# design.net
KiCad netlist of a schematic drawn in Altium Designer
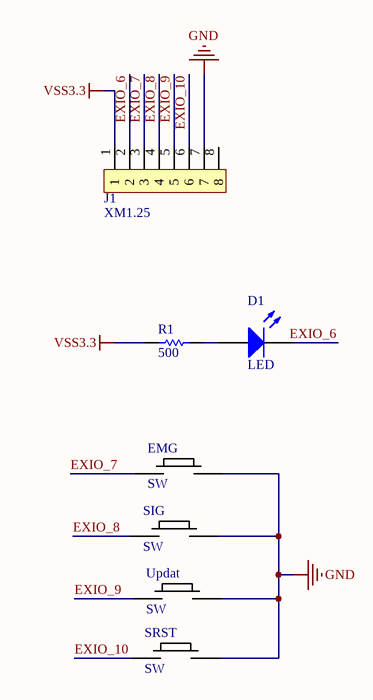
[diagram p0: 遥控器拓展板.SchDoc]

(export (version "E")
  (design (tool "Eeschema 10.0.6"))
  (components
    (comp (ref "D1")
      (value "LED")
      (footprint "LED 0603")
      (description "Typical INFRARED GaAs LED")
      (fields (field (name "PUBLISHER") "Altium Limited"))
      (libsource (lib "Remote") (part "LED"))
    )
    (comp (ref "EMG") (value "SW") (footprint "SW SMD 3x6x2.5") (libsource (lib "船核心板") (part "弹簧开关")))
    (comp (ref "J1")
      (value "XM1.25")
      (footprint "MX1.25 8P")
      (libsource (lib "altium-import") (part "root_0_1X8排针_"))
    )
    (comp (ref "R1")
      (value "500")
      (footprint "R 0603")
      (description "Resistor")
      (fields (field (name "PUBLISHER") "Altium Limited"))
      (libsource (lib "Remote") (part "Res"))
    )
    (comp (ref "SIG") (value "SW") (footprint "SW SMD 3x6x2.5") (libsource (lib "船核心板") (part "弹簧开关")))
    (comp (ref "SRST") (value "SW") (footprint "SW SMD 3x6x2.5") (libsource (lib "船核心板") (part "弹簧开关")))
    (comp (ref "Updat") (value "SW") (footprint "SW SMD 3x6x2.5") (libsource (lib "船核心板") (part "弹簧开关")))
  )
  (nets
    (net (code "1") (name "/EXIO_6") (class "Default")
      (node (ref "D1") (pin "2") (pinfunction "K_2") (pintype "passive"))
      (node (ref "J1") (pin "2") (pinfunction "2_2") (pintype "passive"))
    )
    (net (code "2") (name "/EXIO_7") (class "Default")
      (node (ref "EMG") (pin "1") (pinfunction "1_1") (pintype "passive"))
      (node (ref "J1") (pin "3") (pinfunction "3_3") (pintype "passive"))
    )
    (net (code "3") (name "/EXIO_8") (class "Default")
      (node (ref "J1") (pin "4") (pinfunction "4_4") (pintype "passive"))
      (node (ref "SIG") (pin "1") (pinfunction "1_1") (pintype "passive"))
    )
    (net (code "4") (name "/EXIO_9") (class "Default")
      (node (ref "J1") (pin "5") (pinfunction "5_5") (pintype "passive"))
      (node (ref "Updat") (pin "1") (pinfunction "1_1") (pintype "passive"))
    )
    (net (code "5") (name "/EXIO_10") (class "Default")
      (node (ref "J1") (pin "6") (pinfunction "6_6") (pintype "passive"))
      (node (ref "SRST") (pin "1") (pinfunction "1_1") (pintype "passive"))
    )
    (net (code "6") (name "GND") (class "Default")
      (node (ref "EMG") (pin "2") (pinfunction "2_2") (pintype "passive"))
      (node (ref "J1") (pin "7") (pinfunction "7_7") (pintype "passive"))
      (node (ref "SIG") (pin "2") (pinfunction "2_2") (pintype "passive"))
      (node (ref "SRST") (pin "2") (pinfunction "2_2") (pintype "passive"))
      (node (ref "Updat") (pin "2") (pinfunction "2_2") (pintype "passive"))
    )
    (net (code "7") (name "Net-(D1-A)") (class "Default")
      (node (ref "D1") (pin "1") (pinfunction "A_1") (pintype "passive"))
      (node (ref "R1") (pin "2") (pinfunction "2_2") (pintype "passive"))
    )
    (net (code "8") (name "VSS3.3") (class "Default")
      (node (ref "J1") (pin "1") (pinfunction "1_1") (pintype "passive"))
      (node (ref "R1") (pin "1") (pinfunction "1_1") (pintype "passive"))
    )
    (net (code "9") (name "unconnected-(J1-Pad8)") (class "Default")
      (node (ref "J1") (pin "8") (pinfunction "8_8") (pintype "passive"))
    )
  )
)
